# FalangeNANO.net
KiCad netlist of a schematic drawn in EAGLE
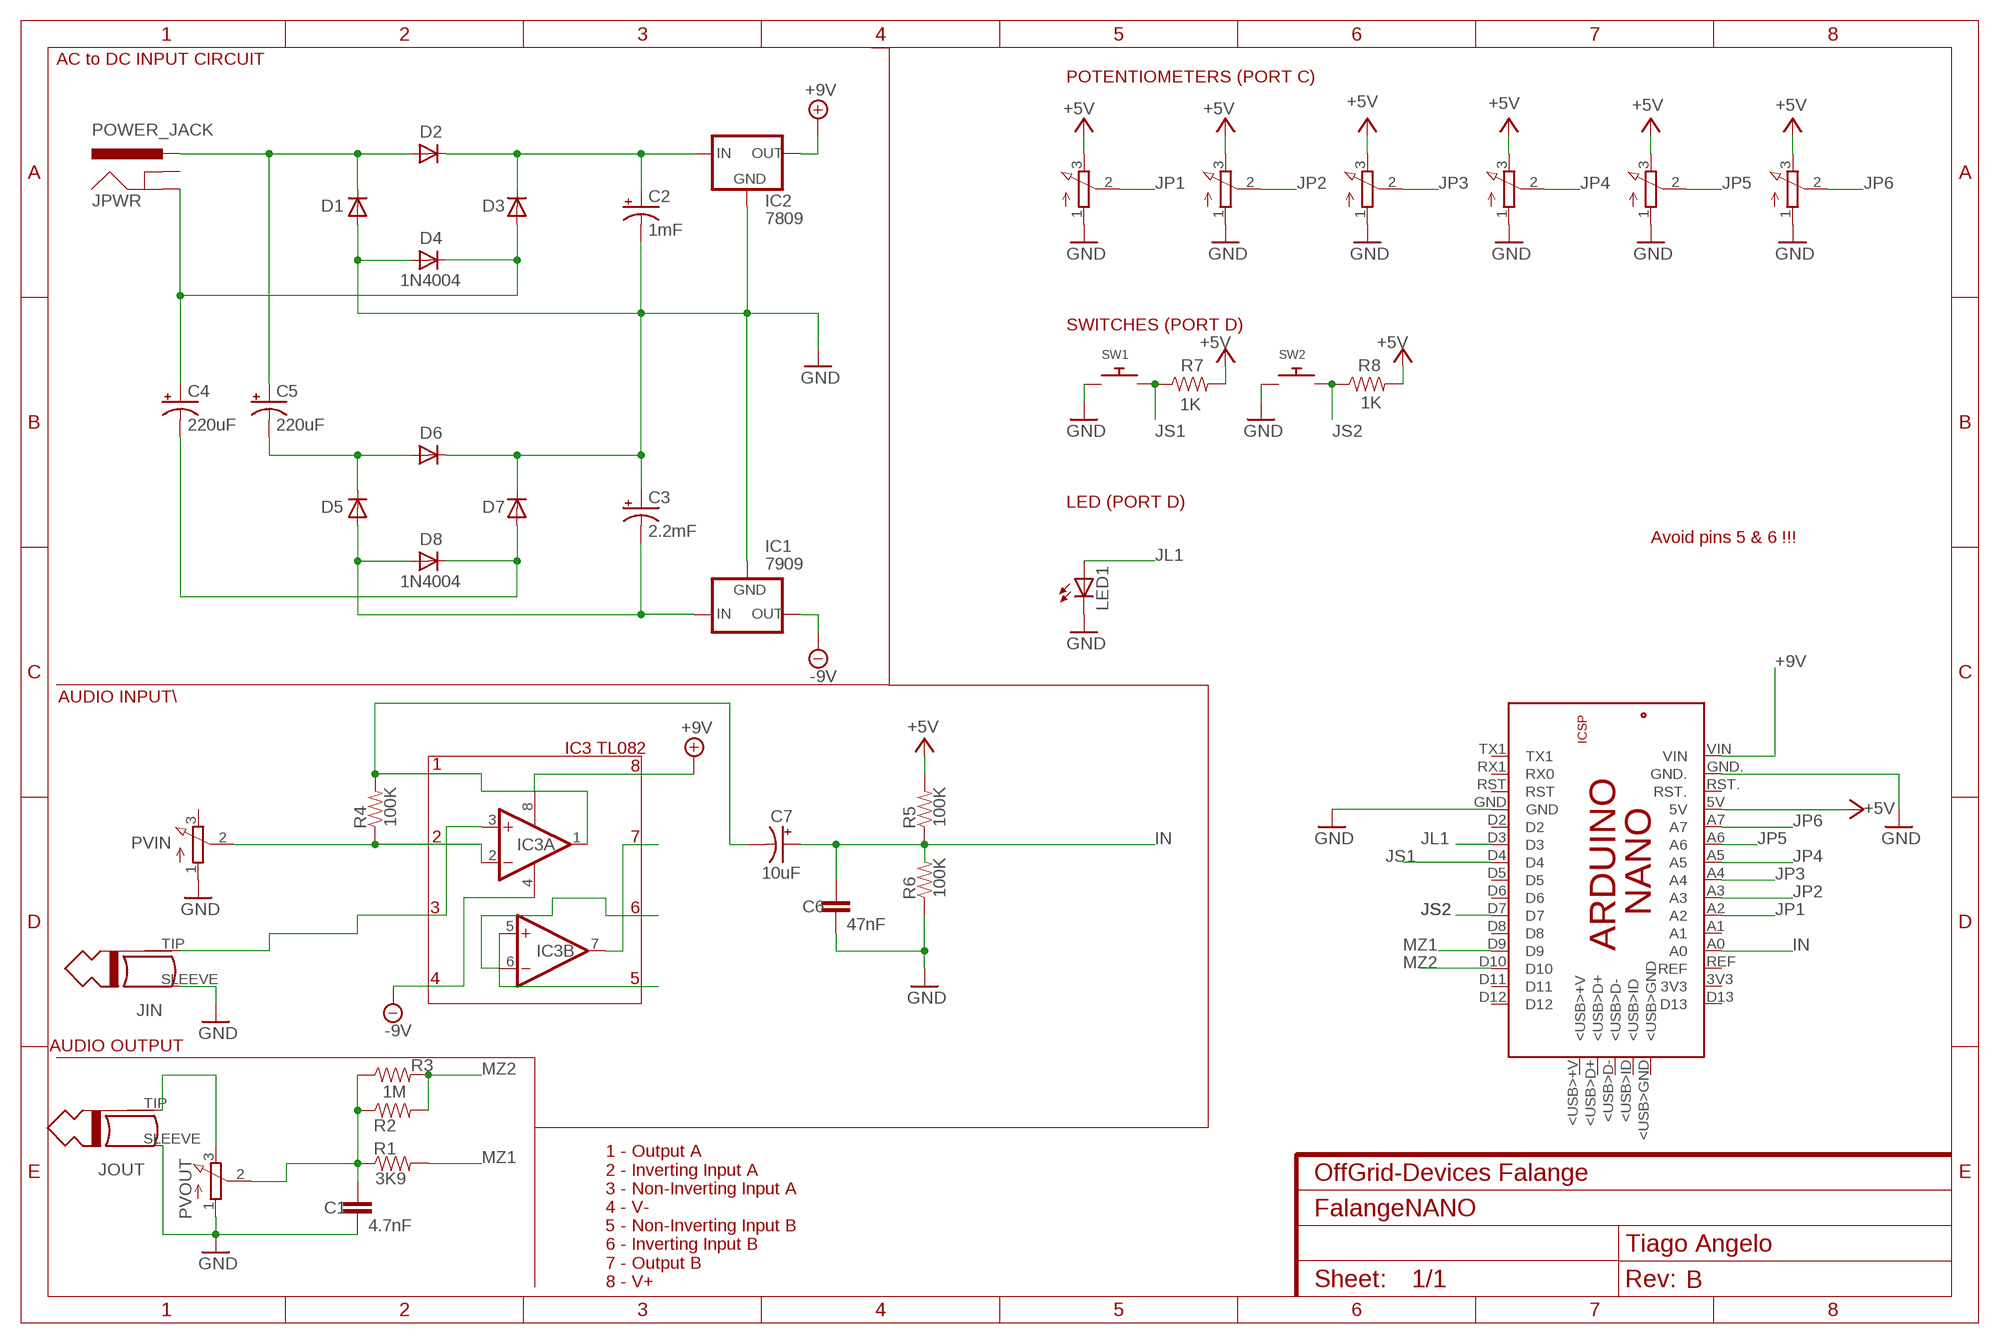
[diagram p0: schematic, sheet 1]

(export (version "E")
  (design (tool "Eeschema 10.0.6"))
  (components
    (comp (ref "C1")
      (value "4.7nF")
      (footprint "eagle-import:C050-025X075")
      (libsource (lib "eagle-import") (part "C-EU050-025X075"))
    )
    (comp (ref "C2")
      (value "1mF")
      (footprint "eagle-import:E30-16")
      (libsource (lib "eagle-import") (part "CPOL-USE30-16AXIAL"))
    )
    (comp (ref "C3")
      (value "2.2mF")
      (footprint "eagle-import:E35-16")
      (libsource (lib "eagle-import") (part "CPOL-USE35-16AXIAL"))
    )
    (comp (ref "C4")
      (value "220uF")
      (footprint "eagle-import:E5-10,5")
      (libsource (lib "eagle-import") (part "rcl_CPOL-USE5-10.5"))
    )
    (comp (ref "C5")
      (value "220uF")
      (footprint "eagle-import:E5-10,5")
      (libsource (lib "eagle-import") (part "rcl_CPOL-USE5-10.5"))
    )
    (comp (ref "C6")
      (value "47nF")
      (footprint "eagle-import:C050-025X075")
      (libsource (lib "eagle-import") (part "C-EU050-025X075"))
    )
    (comp (ref "C7")
      (value "10uF")
      (footprint "eagle-import:E2,5-6")
      (libsource (lib "eagle-import") (part "rcl_CPOL-USE2.5-6"))
    )
    (comp (ref "D1")
      (value "1N4004")
      (footprint "eagle-import:DO41-10")
      (libsource (lib "eagle-import") (part "1N4004"))
    )
    (comp (ref "D2")
      (value "1N4004")
      (footprint "eagle-import:DO41-10")
      (libsource (lib "eagle-import") (part "1N4004"))
    )
    (comp (ref "D3")
      (value "1N4004")
      (footprint "eagle-import:DO41-10")
      (libsource (lib "eagle-import") (part "1N4004"))
    )
    (comp (ref "D4")
      (value "1N4004")
      (footprint "eagle-import:DO41-10")
      (libsource (lib "eagle-import") (part "1N4004"))
    )
    (comp (ref "D5")
      (value "1N4004")
      (footprint "eagle-import:DO41-10")
      (libsource (lib "eagle-import") (part "1N4004"))
    )
    (comp (ref "D6")
      (value "1N4004")
      (footprint "eagle-import:DO41-10")
      (libsource (lib "eagle-import") (part "1N4004"))
    )
    (comp (ref "D7")
      (value "1N4004")
      (footprint "eagle-import:DO41-10")
      (libsource (lib "eagle-import") (part "1N4004"))
    )
    (comp (ref "D8")
      (value "1N4004")
      (footprint "eagle-import:DO41-10")
      (libsource (lib "eagle-import") (part "1N4004"))
    )
    (comp (ref "IC1")
      (value "7909")
      (footprint "eagle-import:79XXL")
      (libsource (lib "eagle-import") (part "79XXL"))
    )
    (comp (ref "IC2")
      (value "7809")
      (footprint "eagle-import:78XXL")
      (libsource (lib "eagle-import") (part "78XXL"))
    )
    (comp (ref "IC3")
      (value "TL082P")
      (footprint "eagle-import:DIL08")
      (libsource (lib "eagle-import") (part "TL082P"))
    )
    (comp (ref "JIN")
      (value "MONO_PLUG")
      (footprint "eagle-import:TWO_PADS")
      (libsource (lib "eagle-import") (part "MONO_PLUG"))
    )
    (comp (ref "JOUT")
      (value "MONO_PLUG")
      (footprint "eagle-import:TWO_PADS")
      (libsource (lib "eagle-import") (part "MONO_PLUG"))
    )
    (comp (ref "JPWR")
      (value "POWER_JACK")
      (footprint "eagle-import:POWER_JACK_PTH")
      (libsource (lib "eagle-import") (part "POWER_JACK"))
    )
    (comp (ref "LED1")
      (value "LED3MM")
      (footprint "eagle-import:LED3MM")
      (libsource (lib "eagle-import") (part "LED3MM"))
    )
    (comp (ref "P1")
      (value "3RP/1610N")
      (footprint "eagle-import:3RP_1610N")
      (libsource (lib "eagle-import") (part "3RP/1610N"))
    )
    (comp (ref "P2")
      (value "3RP/1610N")
      (footprint "eagle-import:3RP_1610N")
      (libsource (lib "eagle-import") (part "3RP/1610N"))
    )
    (comp (ref "P3")
      (value "3RP/1610N")
      (footprint "eagle-import:3RP_1610N")
      (libsource (lib "eagle-import") (part "3RP/1610N"))
    )
    (comp (ref "P4")
      (value "3RP/1610N")
      (footprint "eagle-import:3RP_1610N")
      (libsource (lib "eagle-import") (part "3RP/1610N"))
    )
    (comp (ref "P5")
      (value "3RP/1610N")
      (footprint "eagle-import:3RP_1610N")
      (libsource (lib "eagle-import") (part "3RP/1610N"))
    )
    (comp (ref "P6")
      (value "3RP/1610N")
      (footprint "eagle-import:3RP_1610N")
      (libsource (lib "eagle-import") (part "3RP/1610N"))
    )
    (comp (ref "PCB1")
      (value "ARDUINO_NANO")
      (footprint "eagle-import:ARDUINO_NANO")
      (libsource (lib "eagle-import") (part "ARDUINO_NANO"))
    )
    (comp (ref "PVIN")
      (value "3RP/1610N")
      (footprint "eagle-import:3RP_1610N")
      (libsource (lib "eagle-import") (part "3RP/1610N"))
    )
    (comp (ref "PVOUT")
      (value "3RP/1610N")
      (footprint "eagle-import:3RP_1610N")
      (libsource (lib "eagle-import") (part "3RP/1610N"))
    )
    (comp (ref "R1")
      (value "3K9")
      (footprint "eagle-import:AXIAL-0.3")
      (libsource (lib "eagle-import") (part "1KOHM-HORIZ-1/4W-5%"))
    )
    (comp (ref "R2")
      (value "1M")
      (footprint "eagle-import:AXIAL-0.3")
      (libsource (lib "eagle-import") (part "1KOHM-HORIZ-1/4W-5%"))
    )
    (comp (ref "R3")
      (value "1M")
      (footprint "eagle-import:AXIAL-0.3")
      (libsource (lib "eagle-import") (part "1KOHM-HORIZ-1/4W-5%"))
    )
    (comp (ref "R4")
      (value "100K")
      (footprint "eagle-import:AXIAL-0.3")
      (libsource (lib "eagle-import") (part "1KOHM-HORIZ-1/4W-5%"))
    )
    (comp (ref "R5")
      (value "100K")
      (footprint "eagle-import:AXIAL-0.3")
      (libsource (lib "eagle-import") (part "1KOHM-HORIZ-1/4W-5%"))
    )
    (comp (ref "R6")
      (value "100K")
      (footprint "eagle-import:AXIAL-0.3")
      (libsource (lib "eagle-import") (part "1KOHM-HORIZ-1/4W-5%"))
    )
    (comp (ref "R7")
      (value "1K")
      (footprint "eagle-import:AXIAL-0.3")
      (libsource (lib "eagle-import") (part "1KOHM-HORIZ-1/4W-5%"))
    )
    (comp (ref "R8")
      (value "1K")
      (footprint "eagle-import:AXIAL-0.3")
      (libsource (lib "eagle-import") (part "1KOHM-HORIZ-1/4W-5%"))
    )
    (comp (ref "SW1")
      (value "SWITCH_PUSHBUTTONEVQ-PE")
      (footprint "eagle-import:TACT_PANA-EVQ")
      (libsource (lib "eagle-import") (part "SWITCH_PUSHBUTTONEVQ-PE"))
    )
    (comp (ref "SW2")
      (value "SWITCH_PUSHBUTTONEVQ-PE")
      (footprint "eagle-import:TACT_PANA-EVQ")
      (libsource (lib "eagle-import") (part "SWITCH_PUSHBUTTONEVQ-PE"))
    )
  )
  (nets
    (net (code "1") (name "+5V") (class "Default")
      (node (ref "P1") (pin "3") (pinfunction "E_3") (pintype "passive"))
      (node (ref "P2") (pin "3") (pinfunction "E_3") (pintype "passive"))
      (node (ref "P3") (pin "3") (pinfunction "E_3") (pintype "passive"))
      (node (ref "P4") (pin "3") (pinfunction "E_3") (pintype "passive"))
      (node (ref "P5") (pin "3") (pinfunction "E_3") (pintype "passive"))
      (node (ref "P6") (pin "3") (pinfunction "E_3") (pintype "passive"))
      (node (ref "PCB1") (pin "5V") (pinfunction "5V_5V") (pintype "bidirectional"))
      (node (ref "R5") (pin "P$2") (pinfunction "2_P$2") (pintype "passive"))
      (node (ref "R7") (pin "P$2") (pinfunction "2_P$2") (pintype "passive"))
      (node (ref "R8") (pin "P$2") (pinfunction "2_P$2") (pintype "passive"))
    )
    (net (code "2") (name "+9V") (class "Default")
      (node (ref "IC2") (pin "OUT") (pinfunction "OUT_OUT") (pintype "passive"))
      (node (ref "IC3") (pin "8") (pinfunction "V+_8") (pintype "power_in"))
      (node (ref "PCB1") (pin "VIN") (pinfunction "VIN_VIN") (pintype "bidirectional"))
    )
    (net (code "3") (name "-9V") (class "Default")
      (node (ref "IC1") (pin "OUT") (pinfunction "OUT_OUT") (pintype "passive"))
      (node (ref "IC3") (pin "4") (pinfunction "V-_4") (pintype "power_in"))
    )
    (net (code "4") (name "/IN") (class "Default")
      (node (ref "C6") (pin "1") (pinfunction "1_1") (pintype "passive"))
      (node (ref "C7") (pin "+") (pinfunction "+_+") (pintype "passive"))
      (node (ref "PCB1") (pin "A0") (pinfunction "A0_A0") (pintype "bidirectional"))
      (node (ref "R5") (pin "P$1") (pinfunction "1_P$1") (pintype "passive"))
      (node (ref "R6") (pin "P$2") (pinfunction "2_P$2") (pintype "passive"))
    )
    (net (code "5") (name "/JL1") (class "Default")
      (node (ref "LED1") (pin "A") (pinfunction "A_A") (pintype "passive"))
      (node (ref "PCB1") (pin "D3") (pinfunction "D3_D3") (pintype "bidirectional"))
    )
    (net (code "6") (name "/JP1") (class "Default")
      (node (ref "P1") (pin "2") (pinfunction "S_2") (pintype "passive"))
      (node (ref "PCB1") (pin "A2") (pinfunction "A2_A2") (pintype "bidirectional"))
    )
    (net (code "7") (name "/JP2") (class "Default")
      (node (ref "P2") (pin "2") (pinfunction "S_2") (pintype "passive"))
      (node (ref "PCB1") (pin "A3") (pinfunction "A3_A3") (pintype "bidirectional"))
    )
    (net (code "8") (name "/JP3") (class "Default")
      (node (ref "P3") (pin "2") (pinfunction "S_2") (pintype "passive"))
      (node (ref "PCB1") (pin "A4") (pinfunction "A4_A4") (pintype "bidirectional"))
    )
    (net (code "9") (name "/JP4") (class "Default")
      (node (ref "P4") (pin "2") (pinfunction "S_2") (pintype "passive"))
      (node (ref "PCB1") (pin "A5") (pinfunction "A5_A5") (pintype "bidirectional"))
    )
    (net (code "10") (name "/JP5") (class "Default")
      (node (ref "P5") (pin "2") (pinfunction "S_2") (pintype "passive"))
      (node (ref "PCB1") (pin "A6") (pinfunction "A6_A6") (pintype "bidirectional"))
    )
    (net (code "11") (name "/JP6") (class "Default")
      (node (ref "P6") (pin "2") (pinfunction "S_2") (pintype "passive"))
      (node (ref "PCB1") (pin "A7") (pinfunction "A7_A7") (pintype "bidirectional"))
    )
    (net (code "12") (name "/JS1") (class "Default")
      (node (ref "PCB1") (pin "D4") (pinfunction "D4_D4") (pintype "bidirectional"))
      (node (ref "R7") (pin "P$1") (pinfunction "1_P$1") (pintype "passive"))
      (node (ref "SW1") (pin "P$2") (pinfunction "P$2_P$2") (pintype "passive"))
    )
    (net (code "13") (name "/JS2") (class "Default")
      (node (ref "PCB1") (pin "D7") (pinfunction "D7_D7") (pintype "bidirectional"))
      (node (ref "R8") (pin "P$1") (pinfunction "1_P$1") (pintype "passive"))
      (node (ref "SW2") (pin "P$2") (pinfunction "P$2_P$2") (pintype "passive"))
    )
    (net (code "14") (name "/MZ1") (class "Default")
      (node (ref "PCB1") (pin "D9") (pinfunction "D9_D9") (pintype "bidirectional"))
      (node (ref "R1") (pin "P$2") (pinfunction "2_P$2") (pintype "passive"))
    )
    (net (code "15") (name "/MZ2") (class "Default")
      (node (ref "PCB1") (pin "D10") (pinfunction "D10_D10") (pintype "bidirectional"))
      (node (ref "R2") (pin "P$2") (pinfunction "2_P$2") (pintype "passive"))
      (node (ref "R3") (pin "P$2") (pinfunction "2_P$2") (pintype "passive"))
    )
    (net (code "16") (name "GND") (class "Default")
      (node (ref "C1") (pin "2") (pinfunction "2_2") (pintype "passive"))
      (node (ref "C2") (pin "-") (pinfunction "-_-") (pintype "passive"))
      (node (ref "C3") (pin "+") (pinfunction "+_+") (pintype "passive"))
      (node (ref "C6") (pin "2") (pinfunction "2_2") (pintype "passive"))
      (node (ref "D1") (pin "A") (pinfunction "A_A") (pintype "passive"))
      (node (ref "D4") (pin "A") (pinfunction "A_A") (pintype "passive"))
      (node (ref "D6") (pin "C") (pinfunction "C_C") (pintype "passive"))
      (node (ref "D7") (pin "C") (pinfunction "C_C") (pintype "passive"))
      (node (ref "IC1") (pin "GND") (pinfunction "GND_GND") (pintype "input"))
      (node (ref "IC2") (pin "GND") (pinfunction "GND_GND") (pintype "input"))
      (node (ref "JIN") (pin "SLEEVE") (pinfunction "SLEEVE_SLEEVE") (pintype "passive"))
      (node (ref "JOUT") (pin "SLEEVE") (pinfunction "SLEEVE_SLEEVE") (pintype "passive"))
      (node (ref "LED1") (pin "K") (pinfunction "C_K") (pintype "passive"))
      (node (ref "P1") (pin "1") (pinfunction "A_1") (pintype "passive"))
      (node (ref "P2") (pin "1") (pinfunction "A_1") (pintype "passive"))
      (node (ref "P3") (pin "1") (pinfunction "A_1") (pintype "passive"))
      (node (ref "P4") (pin "1") (pinfunction "A_1") (pintype "passive"))
      (node (ref "P5") (pin "1") (pinfunction "A_1") (pintype "passive"))
      (node (ref "P6") (pin "1") (pinfunction "A_1") (pintype "passive"))
      (node (ref "PCB1") (pin "GND") (pinfunction "GND_GND") (pintype "bidirectional"))
      (node (ref "PCB1") (pin "GND.") (pinfunction "GND._GND.") (pintype "bidirectional"))
      (node (ref "PVIN") (pin "1") (pinfunction "A_1") (pintype "passive"))
      (node (ref "PVOUT") (pin "1") (pinfunction "A_1") (pintype "passive"))
      (node (ref "R6") (pin "P$1") (pinfunction "1_P$1") (pintype "passive"))
      (node (ref "SW1") (pin "P$1") (pinfunction "P$1_P$1") (pintype "passive"))
      (node (ref "SW2") (pin "P$1") (pinfunction "P$1_P$1") (pintype "passive"))
    )
    (net (code "17") (name "Net-(C2-Pad+)") (class "Default")
      (node (ref "C2") (pin "+") (pinfunction "+_+") (pintype "passive"))
      (node (ref "D2") (pin "C") (pinfunction "C_C") (pintype "passive"))
      (node (ref "D3") (pin "C") (pinfunction "C_C") (pintype "passive"))
      (node (ref "IC2") (pin "IN") (pinfunction "IN_IN") (pintype "input"))
    )
    (net (code "18") (name "Net-(C3-Pad-)") (class "Default")
      (node (ref "C3") (pin "-") (pinfunction "-_-") (pintype "passive"))
      (node (ref "D5") (pin "A") (pinfunction "A_A") (pintype "passive"))
      (node (ref "D8") (pin "A") (pinfunction "A_A") (pintype "passive"))
      (node (ref "IC1") (pin "IN") (pinfunction "IN_IN") (pintype "input"))
    )
    (net (code "19") (name "Net-(C4-Pad+)") (class "Default")
      (node (ref "C4") (pin "+") (pinfunction "+_+") (pintype "passive"))
      (node (ref "D3") (pin "A") (pinfunction "A_A") (pintype "passive"))
      (node (ref "D4") (pin "C") (pinfunction "C_C") (pintype "passive"))
      (node (ref "JPWR") (pin "GND") (pinfunction "GND_GND") (pintype "bidirectional"))
    )
    (net (code "20") (name "Net-(C4-Pad-)") (class "Default")
      (node (ref "C4") (pin "-") (pinfunction "-_-") (pintype "passive"))
      (node (ref "D7") (pin "A") (pinfunction "A_A") (pintype "passive"))
      (node (ref "D8") (pin "C") (pinfunction "C_C") (pintype "passive"))
    )
    (net (code "21") (name "Net-(C5-Pad+)") (class "Default")
      (node (ref "C5") (pin "+") (pinfunction "+_+") (pintype "passive"))
      (node (ref "D1") (pin "C") (pinfunction "C_C") (pintype "passive"))
      (node (ref "D2") (pin "A") (pinfunction "A_A") (pintype "passive"))
      (node (ref "JPWR") (pin "PWR") (pinfunction "PWR_PWR") (pintype "bidirectional"))
    )
    (net (code "22") (name "Net-(C5-Pad-)") (class "Default")
      (node (ref "C5") (pin "-") (pinfunction "-_-") (pintype "passive"))
      (node (ref "D5") (pin "C") (pinfunction "C_C") (pintype "passive"))
      (node (ref "D6") (pin "A") (pinfunction "A_A") (pintype "passive"))
    )
    (net (code "23") (name "Net-(IC3A-+IN)") (class "Default")
      (node (ref "IC3") (pin "3") (pinfunction "+IN_3") (pintype "input"))
      (node (ref "JIN") (pin "TIP") (pinfunction "TIP_TIP") (pintype "passive"))
    )
    (net (code "24") (name "Net-(IC3A--IN)") (class "Default")
      (node (ref "IC3") (pin "2") (pinfunction "-IN_2") (pintype "input"))
      (node (ref "PVIN") (pin "2") (pinfunction "S_2") (pintype "passive"))
      (node (ref "R4") (pin "P$1") (pinfunction "1_P$1") (pintype "passive"))
    )
    (net (code "25") (name "Net-(IC3A-OUT)") (class "Default")
      (node (ref "C7") (pin "-") (pinfunction "-_-") (pintype "passive"))
      (node (ref "IC3") (pin "1") (pinfunction "OUT_1") (pintype "output"))
      (node (ref "R4") (pin "P$2") (pinfunction "2_P$2") (pintype "passive"))
    )
    (net (code "26") (name "Net-(PVOUT-E)") (class "Default")
      (node (ref "JOUT") (pin "TIP") (pinfunction "TIP_TIP") (pintype "passive"))
      (node (ref "PVOUT") (pin "3") (pinfunction "E_3") (pintype "passive"))
    )
    (net (code "27") (name "Net-(PVOUT-S)") (class "Default")
      (node (ref "C1") (pin "1") (pinfunction "1_1") (pintype "passive"))
      (node (ref "PVOUT") (pin "2") (pinfunction "S_2") (pintype "passive"))
      (node (ref "R1") (pin "P$1") (pinfunction "1_P$1") (pintype "passive"))
      (node (ref "R2") (pin "P$1") (pinfunction "1_P$1") (pintype "passive"))
      (node (ref "R3") (pin "P$1") (pinfunction "1_P$1") (pintype "passive"))
    )
    (net (code "28") (name "unconnected-(IC3B-+IN-Pad5)") (class "Default")
      (node (ref "IC3") (pin "5") (pinfunction "+IN_5") (pintype "input"))
    )
    (net (code "29") (name "unconnected-(IC3B--IN-Pad6)") (class "Default")
      (node (ref "IC3") (pin "6") (pinfunction "-IN_6") (pintype "input"))
    )
    (net (code "30") (name "unconnected-(IC3B-OUT-Pad7)") (class "Default")
      (node (ref "IC3") (pin "7") (pinfunction "OUT_7") (pintype "output"))
    )
    (net (code "31") (name "unconnected-(JPWR-PadGNDBREAK)") (class "Default")
      (node (ref "JPWR") (pin "GNDBREAK") (pinfunction "GNDBREAK_GNDBREAK") (pintype "bidirectional"))
    )
    (net (code "32") (name "unconnected-(PCB1-Pad3V3)") (class "Default")
      (node (ref "PCB1") (pin "3V3") (pinfunction "3V3_3V3") (pintype "bidirectional"))
    )
    (net (code "33") (name "unconnected-(PCB1-Pad5V.)") (class "Default")
      (node (ref "PCB1") (pin "5V.") (pinfunction "5V._5V.") (pintype "bidirectional"))
    )
    (net (code "34") (name "unconnected-(PCB1-Pad<USB>+V)") (class "Default")
      (node (ref "PCB1") (pin "<USB>+V") (pinfunction "<USB>+V_<USB>+V") (pintype "bidirectional"))
    )
    (net (code "35") (name "unconnected-(PCB1-Pad<USB>D+)") (class "Default")
      (node (ref "PCB1") (pin "<USB>D+") (pinfunction "<USB>D+_<USB>D+") (pintype "bidirectional"))
    )
    (net (code "36") (name "unconnected-(PCB1-Pad<USB>D-)") (class "Default")
      (node (ref "PCB1") (pin "<USB>D-") (pinfunction "<USB>D-_<USB>D-") (pintype "bidirectional"))
    )
    (net (code "37") (name "unconnected-(PCB1-Pad<USB>GND)") (class "Default")
      (node (ref "PCB1") (pin "<USB>GND") (pinfunction "<USB>GND_<USB>GND") (pintype "bidirectional"))
    )
    (net (code "38") (name "unconnected-(PCB1-Pad<USB>ID)") (class "Default")
      (node (ref "PCB1") (pin "<USB>ID") (pinfunction "<USB>ID_<USB>ID") (pintype "bidirectional"))
    )
    (net (code "39") (name "unconnected-(PCB1-PadA1)") (class "Default")
      (node (ref "PCB1") (pin "A1") (pinfunction "A1_A1") (pintype "bidirectional"))
    )
    (net (code "40") (name "unconnected-(PCB1-PadD2)") (class "Default")
      (node (ref "PCB1") (pin "D2") (pinfunction "D2_D2") (pintype "bidirectional"))
    )
    (net (code "41") (name "unconnected-(PCB1-PadD5)") (class "Default")
      (node (ref "PCB1") (pin "D5") (pinfunction "D5_D5") (pintype "bidirectional"))
    )
    (net (code "42") (name "unconnected-(PCB1-PadD6)") (class "Default")
      (node (ref "PCB1") (pin "D6") (pinfunction "D6_D6") (pintype "bidirectional"))
    )
    (net (code "43") (name "unconnected-(PCB1-PadD8)") (class "Default")
      (node (ref "PCB1") (pin "D8") (pinfunction "D8_D8") (pintype "bidirectional"))
    )
    (net (code "44") (name "unconnected-(PCB1-PadD11)") (class "Default")
      (node (ref "PCB1") (pin "D11") (pinfunction "D11_D11") (pintype "bidirectional"))
    )
    (net (code "45") (name "unconnected-(PCB1-PadD12)") (class "Default")
      (node (ref "PCB1") (pin "D12") (pinfunction "D12_D12") (pintype "bidirectional"))
    )
    (net (code "46") (name "unconnected-(PCB1-PadD13)") (class "Default")
      (node (ref "PCB1") (pin "D13") (pinfunction "D13_D13") (pintype "bidirectional"))
    )
    (net (code "47") (name "unconnected-(PCB1-PadGND_)") (class "Default")
      (node (ref "PCB1") (pin "GND_") (pinfunction "GND__GND_") (pintype "bidirectional"))
    )
    (net (code "48") (name "unconnected-(PCB1-PadMISO)") (class "Default")
      (node (ref "PCB1") (pin "MISO") (pinfunction "MISO_MISO") (pintype "bidirectional"))
    )
    (net (code "49") (name "unconnected-(PCB1-PadMOSI)") (class "Default")
      (node (ref "PCB1") (pin "MOSI") (pinfunction "MOSI_MOSI") (pintype "bidirectional"))
    )
    (net (code "50") (name "unconnected-(PCB1-PadREF)") (class "Default")
      (node (ref "PCB1") (pin "REF") (pinfunction "REF_REF") (pintype "bidirectional"))
    )
    (net (code "51") (name "unconnected-(PCB1-PadRESET..)") (class "Default")
      (node (ref "PCB1") (pin "RESET..") (pinfunction "RESET.._RESET..") (pintype "bidirectional"))
    )
    (net (code "52") (name "unconnected-(PCB1-PadRST)") (class "Default")
      (node (ref "PCB1") (pin "RST") (pinfunction "RST_RST") (pintype "bidirectional"))
    )
    (net (code "53") (name "unconnected-(PCB1-PadRST.)") (class "Default")
      (node (ref "PCB1") (pin "RST.") (pinfunction "RST._RST.") (pintype "bidirectional"))
    )
    (net (code "54") (name "unconnected-(PCB1-PadSCK)") (class "Default")
      (node (ref "PCB1") (pin "SCK") (pinfunction "SCK_SCK") (pintype "bidirectional"))
    )
    (net (code "55") (name "unconnected-(PCB1-PadTX1)") (class "Default")
      (node (ref "PCB1") (pin "TX1") (pinfunction "TX1_TX1") (pintype "bidirectional"))
    )
    (net (code "56") (name "unconnected-(PCB1-RX0-PadRX1)") (class "Default")
      (node (ref "PCB1") (pin "RX1") (pinfunction "RX0_RX1") (pintype "bidirectional"))
    )
    (net (code "57") (name "unconnected-(PVIN-E-Pad3)") (class "Default")
      (node (ref "PVIN") (pin "3") (pinfunction "E_3") (pintype "passive"))
    )
  )
)
